# UART_to_TTL.net
KiCad netlist of a schematic drawn in Altium Designer
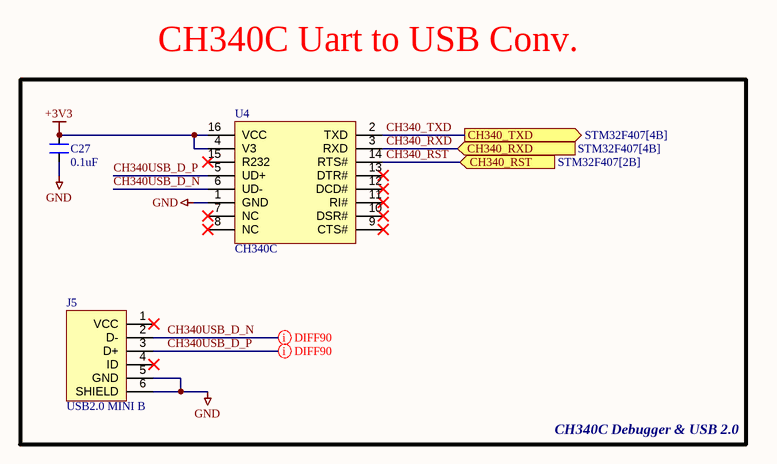
[diagram p0: UART to TTL.SchDoc]

(export (version "E")
  (design (tool "Eeschema 10.0.6"))
  (components
    (comp (ref "C27")
      (value "0.1uF")
      (footprint "CAP_0805")
      (description "0.1µF ±5% 50V Ceramic Capacitor X7R 0805 (2012 Metric)")
      (fields
        (field (name "MANUFACTURER") "AVX Corporation")
        (field (name "MANUFACTURER PART NUMBER") "08055C104JAT4A")
      )
      (libsource (lib "ESTEEMPCBLIB") (part "CAP_0.1uF-50V-5%-0805"))
    )
    (comp (ref "J5")
      (value "USB2.0 MINI B")
      (footprint "CON_690-005-299-043")
      (description "USB - mini B USB 2.0 Receptacle Connector 5 Position Surface Mount, Right Angle")
      (fields
        (field (name "MANUFACTURER") "EDAC")
        (field (name "MANUFACTURER PART NUMBER") "690-005-299-043")
      )
      (libsource (lib "ESTEEMPCBLIB") (part "CON_USB2.0-MINIB-SMD"))
    )
    (comp (ref "U4")
      (value "CH340C")
      (footprint "SOIC16_50_284_25X90_SMT")
      (description "USB Bridge, USB to UART USB 2.0 UART Interface")
      (fields (field (name "MANUFACTURER") "Olimex"))
      (libsource (lib "ESTEEMPCBLIB") (part "IC_CH340C"))
    )
  )
  (nets
    (net (code "1") (name "+3V3") (class "Default")
      (node (ref "C27") (pin "2") (pinfunction "2_2") (pintype "passive"))
      (node (ref "U4") (pin "16") (pinfunction "VCC_16") (pintype "passive"))
      (node (ref "U4") (pin "4") (pinfunction "V3_4") (pintype "passive"))
    )
    (net (code "2") (name "/CH340USB_D_N") (class "Default")
      (node (ref "J5") (pin "2") (pinfunction "D-_2") (pintype "passive"))
      (node (ref "U4") (pin "6") (pinfunction "UD-_6") (pintype "passive"))
    )
    (net (code "3") (name "/CH340USB_D_P") (class "Default")
      (node (ref "J5") (pin "3") (pinfunction "D+_3") (pintype "passive"))
      (node (ref "U4") (pin "5") (pinfunction "UD+_5") (pintype "passive"))
    )
    (net (code "4") (name "/CH340_RST") (class "Default")
      (node (ref "U4") (pin "14") (pinfunction "RTS#_14") (pintype "passive"))
    )
    (net (code "5") (name "/CH340_RXD") (class "Default")
      (node (ref "U4") (pin "3") (pinfunction "RXD_3") (pintype "passive"))
    )
    (net (code "6") (name "/CH340_TXD") (class "Default")
      (node (ref "U4") (pin "2") (pinfunction "TXD_2") (pintype "passive"))
    )
    (net (code "7") (name "GND") (class "Default")
      (node (ref "C27") (pin "1") (pinfunction "1_1") (pintype "passive"))
      (node (ref "J5") (pin "5") (pinfunction "GND_5") (pintype "passive"))
      (node (ref "J5") (pin "6") (pinfunction "SHIELD_6") (pintype "passive"))
      (node (ref "U4") (pin "1") (pinfunction "GND_1") (pintype "passive"))
    )
    (net (code "8") (name "unconnected-(J5-ID-Pad4)") (class "Default")
      (node (ref "J5") (pin "4") (pinfunction "ID_4") (pintype "passive+no_connect"))
    )
    (net (code "9") (name "unconnected-(J5-VCC-Pad1)") (class "Default")
      (node (ref "J5") (pin "1") (pinfunction "VCC_1") (pintype "passive+no_connect"))
    )
    (net (code "10") (name "unconnected-(U4-CTS#-Pad9)") (class "Default")
      (node (ref "U4") (pin "9") (pinfunction "CTS#_9") (pintype "passive+no_connect"))
    )
    (net (code "11") (name "unconnected-(U4-DCD#-Pad12)") (class "Default")
      (node (ref "U4") (pin "12") (pinfunction "DCD#_12") (pintype "passive+no_connect"))
    )
    (net (code "12") (name "unconnected-(U4-DSR#-Pad10)") (class "Default")
      (node (ref "U4") (pin "10") (pinfunction "DSR#_10") (pintype "passive+no_connect"))
    )
    (net (code "13") (name "unconnected-(U4-DTR#-Pad13)") (class "Default")
      (node (ref "U4") (pin "13") (pinfunction "DTR#_13") (pintype "passive+no_connect"))
    )
    (net (code "14") (name "unconnected-(U4-NC-Pad7)") (class "Default")
      (node (ref "U4") (pin "7") (pinfunction "NC_7") (pintype "passive+no_connect"))
    )
    (net (code "15") (name "unconnected-(U4-NC-Pad8)") (class "Default")
      (node (ref "U4") (pin "8") (pinfunction "NC_8") (pintype "passive+no_connect"))
    )
    (net (code "16") (name "unconnected-(U4-R232-Pad15)") (class "Default")
      (node (ref "U4") (pin "15") (pinfunction "R232_15") (pintype "passive+no_connect"))
    )
    (net (code "17") (name "unconnected-(U4-RI#-Pad11)") (class "Default")
      (node (ref "U4") (pin "11") (pinfunction "RI#_11") (pintype "passive+no_connect"))
    )
  )
)
